# full_motor.net
KiCad netlist of a schematic drawn in EAGLE
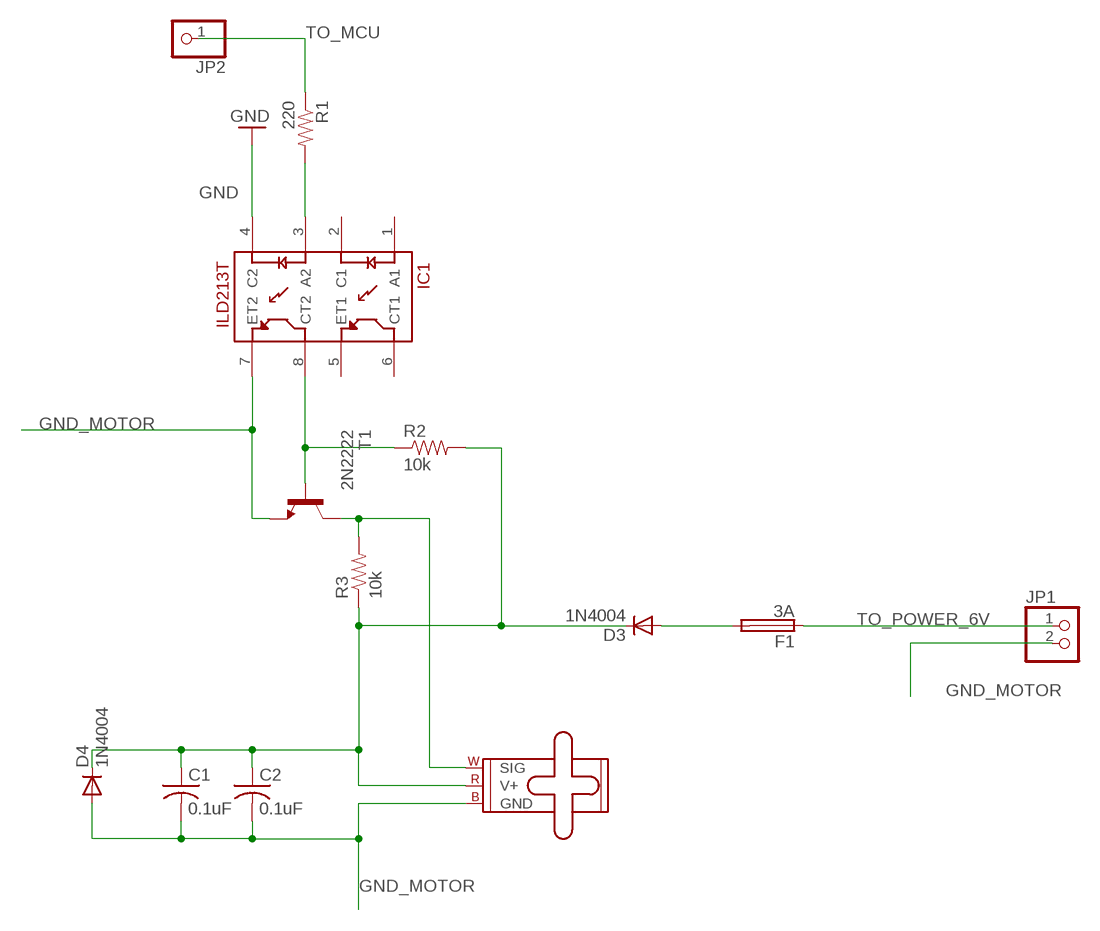
[diagram p0: schematic, sheet 1]

(export (version "E")
  (design (tool "Eeschema 10.0.6"))
  (components
    (comp (ref "C1")
      (value "0.1uF")
      (footprint "eagle-import:C025-024X044")
      (libsource (lib "eagle-import") (part "C-US025-024X044"))
    )
    (comp (ref "C2")
      (value "0.1uF")
      (footprint "eagle-import:C025-024X044")
      (libsource (lib "eagle-import") (part "C-US025-024X044"))
    )
    (comp (ref "D3")
      (value "1N4004")
      (footprint "eagle-import:DO41-10")
      (libsource (lib "eagle-import") (part "1N4004"))
    )
    (comp (ref "D4")
      (value "1N4004")
      (footprint "eagle-import:DO41-10")
      (libsource (lib "eagle-import") (part "1N4004"))
    )
    (comp (ref "F1")
      (value "3A")
      (footprint "eagle-import:TE5")
      (libsource (lib "eagle-import") (part "TE5"))
    )
    (comp (ref "IC1")
      (value "ILD213T")
      (footprint "eagle-import:SO08")
      (libsource (lib "eagle-import") (part "ILD213T"))
    )
    (comp (ref "JP1")
      (value "PINHD-1X2")
      (footprint "eagle-import:1X02")
      (libsource (lib "eagle-import") (part "PINHD-1X2"))
    )
    (comp (ref "JP2")
      (value "PINHD-1X1")
      (footprint "eagle-import:1X01")
      (libsource (lib "eagle-import") (part "PINHD-1X1"))
    )
    (comp (ref "M1")
      (value "SMALL_SERVO")
      (footprint "eagle-import:1X03")
      (libsource (lib "eagle-import") (part "SMALL_SERVO"))
    )
    (comp (ref "R1")
      (value "220")
      (footprint "eagle-import:1206")
      (libsource (lib "eagle-import") (part "RESISTOR1206"))
    )
    (comp (ref "R2")
      (value "10k")
      (footprint "eagle-import:1206")
      (libsource (lib "eagle-import") (part "RESISTOR1206"))
    )
    (comp (ref "R3")
      (value "10k")
      (footprint "eagle-import:1206")
      (libsource (lib "eagle-import") (part "RESISTOR1206"))
    )
    (comp (ref "T1")
      (value "2N2222")
      (footprint "eagle-import:TO92-EBC-OVAL")
      (libsource (lib "eagle-import") (part "2N2222"))
    )
  )
  (nets
    (net (code "1") (name "/GND_MOTOR") (class "Default")
      (node (ref "C1") (pin "2") (pinfunction "2_2") (pintype "passive"))
      (node (ref "C2") (pin "2") (pinfunction "2_2") (pintype "passive"))
      (node (ref "D4") (pin "A") (pinfunction "A_A") (pintype "passive"))
      (node (ref "IC1") (pin "7") (pinfunction "ET2_7") (pintype "bidirectional"))
      (node (ref "JP1") (pin "2") (pinfunction "2_2") (pintype "passive"))
      (node (ref "M1") (pin "3") (pinfunction "GND_3") (pintype "bidirectional"))
      (node (ref "T1") (pin "E") (pinfunction "E_E") (pintype "passive"))
    )
    (net (code "2") (name "/TO_MCU") (class "Default")
      (node (ref "JP2") (pin "1") (pinfunction "1_1") (pintype "passive"))
      (node (ref "R1") (pin "1") (pinfunction "1_1") (pintype "passive"))
    )
    (net (code "3") (name "/TO_POWER_6V") (class "Default")
      (node (ref "F1") (pin "1") (pinfunction "1_1") (pintype "passive"))
      (node (ref "JP1") (pin "1") (pinfunction "1_1") (pintype "passive"))
    )
    (net (code "4") (name "GND") (class "Default")
      (node (ref "IC1") (pin "4") (pinfunction "C2_4") (pintype "bidirectional"))
    )
    (net (code "5") (name "Net-(D3-PadA)") (class "Default")
      (node (ref "D3") (pin "A") (pinfunction "A_A") (pintype "passive"))
      (node (ref "F1") (pin "2") (pinfunction "2_2") (pintype "passive"))
    )
    (net (code "6") (name "Net-(IC1-A2)") (class "Default")
      (node (ref "IC1") (pin "3") (pinfunction "A2_3") (pintype "bidirectional"))
      (node (ref "R1") (pin "2") (pinfunction "2_2") (pintype "passive"))
    )
    (net (code "7") (name "Net-(IC1-CT2)") (class "Default")
      (node (ref "IC1") (pin "8") (pinfunction "CT2_8") (pintype "bidirectional"))
      (node (ref "R2") (pin "1") (pinfunction "1_1") (pintype "passive"))
      (node (ref "T1") (pin "B") (pinfunction "B_B") (pintype "passive"))
    )
    (net (code "8") (name "Net-(M1-SIG)") (class "Default")
      (node (ref "M1") (pin "1") (pinfunction "SIG_1") (pintype "bidirectional"))
      (node (ref "R3") (pin "2") (pinfunction "2_2") (pintype "passive"))
      (node (ref "T1") (pin "C") (pinfunction "C_C") (pintype "passive"))
    )
    (net (code "9") (name "Net-(M1-V+)") (class "Default")
      (node (ref "C1") (pin "1") (pinfunction "1_1") (pintype "passive"))
      (node (ref "C2") (pin "1") (pinfunction "1_1") (pintype "passive"))
      (node (ref "D3") (pin "C") (pinfunction "C_C") (pintype "passive"))
      (node (ref "D4") (pin "C") (pinfunction "C_C") (pintype "passive"))
      (node (ref "M1") (pin "2") (pinfunction "V+_2") (pintype "bidirectional"))
      (node (ref "R2") (pin "2") (pinfunction "2_2") (pintype "passive"))
      (node (ref "R3") (pin "1") (pinfunction "1_1") (pintype "passive"))
    )
    (net (code "10") (name "unconnected-(IC1-A1-Pad1)") (class "Default")
      (node (ref "IC1") (pin "1") (pinfunction "A1_1") (pintype "bidirectional"))
    )
    (net (code "11") (name "unconnected-(IC1-C1-Pad2)") (class "Default")
      (node (ref "IC1") (pin "2") (pinfunction "C1_2") (pintype "bidirectional"))
    )
    (net (code "12") (name "unconnected-(IC1-CT1-Pad6)") (class "Default")
      (node (ref "IC1") (pin "6") (pinfunction "CT1_6") (pintype "bidirectional"))
    )
    (net (code "13") (name "unconnected-(IC1-ET1-Pad5)") (class "Default")
      (node (ref "IC1") (pin "5") (pinfunction "ET1_5") (pintype "bidirectional"))
    )
  )
)
